# buslamp-r2.net
KiCad netlist of a schematic drawn in EAGLE
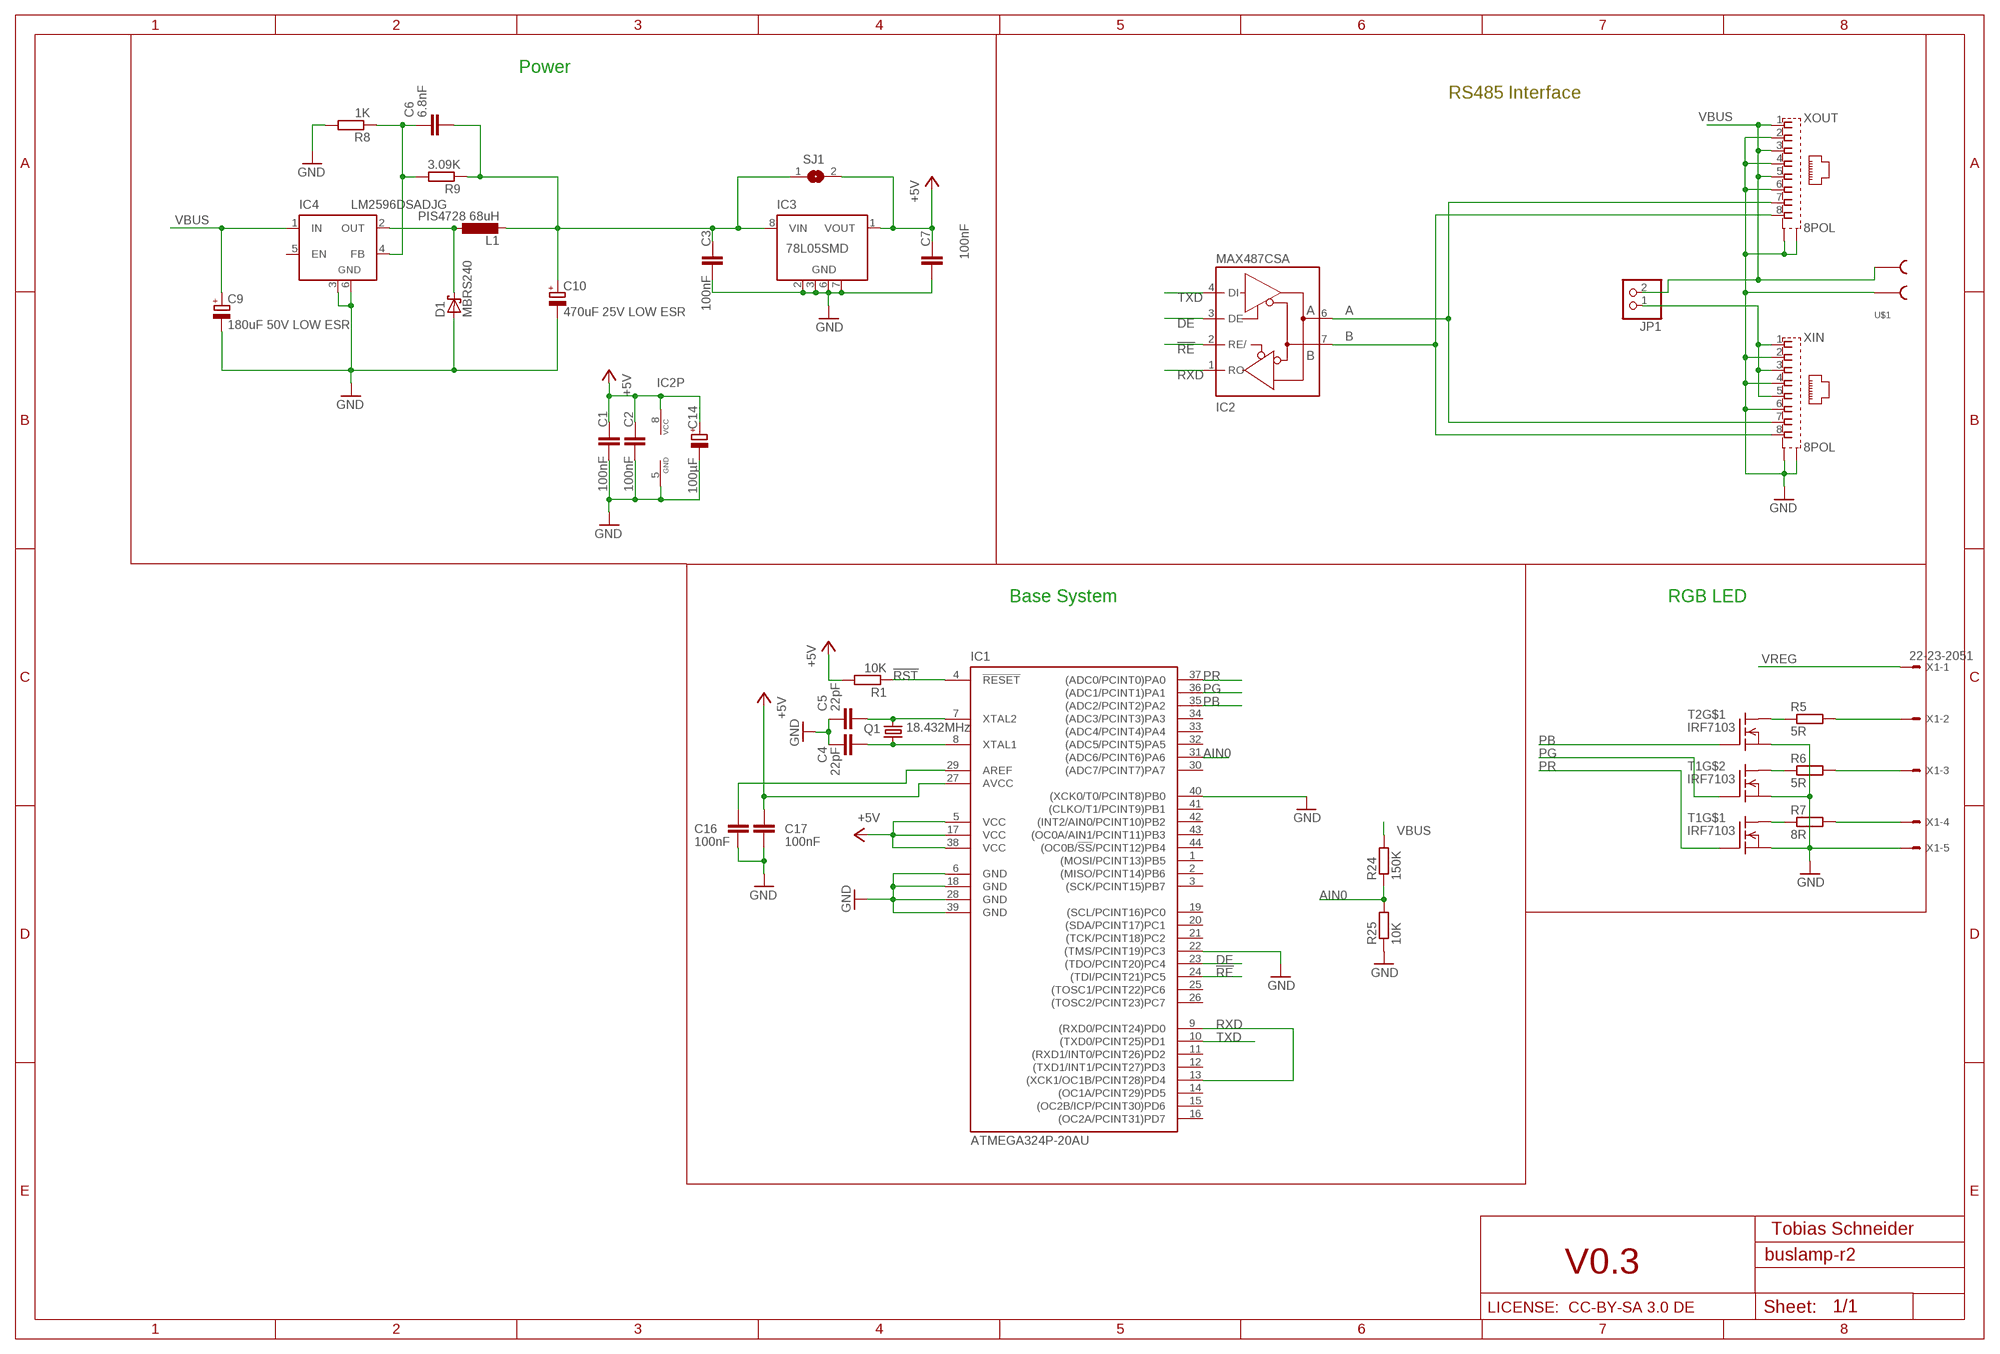
[diagram p0: schematic, sheet 1]

(export (version "E")
  (design (tool "Eeschema 10.0.6"))
  (components
    (comp (ref "C1")
      (value "100nF")
      (footprint "eagle-import:C0805K")
      (libsource (lib "eagle-import") (part "C-EUC0805K"))
    )
    (comp (ref "C2")
      (value "100nF")
      (footprint "eagle-import:C0805K")
      (libsource (lib "eagle-import") (part "C-EUC0805K"))
    )
    (comp (ref "C3")
      (value "100nF")
      (footprint "eagle-import:C0805K")
      (libsource (lib "eagle-import") (part "C-EUC0805K"))
    )
    (comp (ref "C4")
      (value "22pF")
      (footprint "eagle-import:C0805K")
      (libsource (lib "eagle-import") (part "C-EUC0805K"))
    )
    (comp (ref "C5")
      (value "22pF")
      (footprint "eagle-import:C0805K")
      (libsource (lib "eagle-import") (part "C-EUC0805K"))
    )
    (comp (ref "C6")
      (value "6.8nF")
      (footprint "eagle-import:C0805K")
      (libsource (lib "eagle-import") (part "C-EUC0805K"))
    )
    (comp (ref "C7")
      (value "100nF")
      (footprint "eagle-import:C0805K")
      (libsource (lib "eagle-import") (part "C-EUC0805K"))
    )
    (comp (ref "C9")
      (value "180uF 50V LOW ESR")
      (footprint "eagle-import:E3,5-8")
      (libsource (lib "eagle-import") (part "CPOL-EUE3.5-8"))
    )
    (comp (ref "C10")
      (value "470uF 25V LOW ESR")
      (footprint "eagle-import:E2,5-7")
      (libsource (lib "eagle-import") (part "CPOL-EUE2.5-7"))
    )
    (comp (ref "C14")
      (value "100µF")
      (footprint "eagle-import:E2,5-6")
      (libsource (lib "eagle-import") (part "CPOL-EUE2.5-6"))
    )
    (comp (ref "C16")
      (value "100nF")
      (footprint "eagle-import:C0805")
      (libsource (lib "eagle-import") (part "C-EUC0805"))
    )
    (comp (ref "C17")
      (value "100nF")
      (footprint "eagle-import:C0805")
      (libsource (lib "eagle-import") (part "C-EUC0805"))
    )
    (comp (ref "D1")
      (value "MBRS240")
      (footprint "eagle-import:SMB")
      (libsource (lib "eagle-import") (part "MBRS130LT3"))
    )
    (comp (ref "IC1")
      (value "ATMEGA324P-20AU")
      (footprint "eagle-import:TQFP44")
      (libsource (lib "eagle-import") (part "MEGA164P/324P/644P-AU"))
    )
    (comp (ref "IC2")
      (value "MAX487CSA")
      (footprint "eagle-import:SO08")
      (libsource (lib "eagle-import") (part "MAX481CSA"))
    )
    (comp (ref "IC3")
      (value "78L05SMD")
      (footprint "eagle-import:SO08")
      (libsource (lib "eagle-import") (part "78LSMD05"))
    )
    (comp (ref "IC4")
      (value "LM2596DSADJG")
      (footprint "eagle-import:TO263-5")
      (libsource (lib "eagle-import") (part "LM2596S"))
    )
    (comp (ref "JP1")
      (value "PINHD-1X2")
      (footprint "eagle-import:1X02")
      (libsource (lib "eagle-import") (part "PINHD-1X2"))
    )
    (comp (ref "L1")
      (value "PIS4728 68uH")
      (footprint "eagle-import:PIS4728")
      (libsource (lib "eagle-import") (part "PSI4728"))
    )
    (comp (ref "Q1")
      (value "18.432MHz")
      (footprint "eagle-import:HC49_S")
      (libsource (lib "eagle-import") (part "CRYTALHC49S"))
    )
    (comp (ref "R1")
      (value "10K")
      (footprint "eagle-import:M0805")
      (libsource (lib "eagle-import") (part "R-EU_M0805"))
    )
    (comp (ref "R5")
      (value "5R")
      (footprint "eagle-import:0617_17")
      (libsource (lib "eagle-import") (part "rclml_R-EU_0617/17"))
    )
    (comp (ref "R6")
      (value "5R")
      (footprint "eagle-import:0617_17")
      (libsource (lib "eagle-import") (part "rclml_R-EU_0617/17"))
    )
    (comp (ref "R7")
      (value "8R")
      (footprint "eagle-import:0617_17")
      (libsource (lib "eagle-import") (part "rclml_R-EU_0617/17"))
    )
    (comp (ref "R8")
      (value "1K")
      (footprint "eagle-import:M0805")
      (libsource (lib "eagle-import") (part "R-EU_M0805"))
    )
    (comp (ref "R9")
      (value "3.09K")
      (footprint "eagle-import:M0805")
      (libsource (lib "eagle-import") (part "R-EU_M0805"))
    )
    (comp (ref "R24")
      (value "150K")
      (footprint "eagle-import:R0805")
      (libsource (lib "eagle-import") (part "R-EU_R0805"))
    )
    (comp (ref "R25")
      (value "10K")
      (footprint "eagle-import:R0805")
      (libsource (lib "eagle-import") (part "R-EU_R0805"))
    )
    (comp (ref "SJ1") (value "SJ") (footprint "eagle-import:SJ") (libsource (lib "eagle-import") (part "SJ")))
    (comp (ref "T1")
      (value "IRF7103")
      (footprint "eagle-import:SO-8")
      (libsource (lib "eagle-import") (part "IRF7103"))
    )
    (comp (ref "T2")
      (value "IRF7103")
      (footprint "eagle-import:SO-8")
      (libsource (lib "eagle-import") (part "IRF7103"))
    )
    (comp (ref "U$1")
      (value "STL-266-2")
      (footprint "eagle-import:STL-266-2")
      (libsource (lib "eagle-import") (part "STL-266-2"))
    )
    (comp (ref "X1")
      (value "22-23-2051")
      (footprint "eagle-import:22-23-2051")
      (fields (field (name "MF") "MOLEX"))
      (libsource (lib "eagle-import") (part "22-23-2051"))
    )
    (comp (ref "XIN")
      (value "8POL")
      (footprint "eagle-import:8POL")
      (libsource (lib "eagle-import") (part "8POL"))
    )
    (comp (ref "XOUT")
      (value "8POL")
      (footprint "eagle-import:8POL")
      (libsource (lib "eagle-import") (part "8POL"))
    )
  )
  (nets
    (net (code "1") (name "+5V") (class "Default")
      (node (ref "C1") (pin "1") (pinfunction "1_1") (pintype "passive"))
      (node (ref "C14") (pin "+") (pinfunction "+_+") (pintype "passive"))
      (node (ref "C17") (pin "2") (pinfunction "2_2") (pintype "passive"))
      (node (ref "C2") (pin "1") (pinfunction "1_1") (pintype "passive"))
      (node (ref "C7") (pin "1") (pinfunction "1_1") (pintype "passive"))
      (node (ref "IC1") (pin "17") (pinfunction "VCC_17") (pintype "power_in"))
      (node (ref "IC1") (pin "27") (pinfunction "AVCC_27") (pintype "power_in"))
      (node (ref "IC1") (pin "38") (pinfunction "VCC_38") (pintype "power_in"))
      (node (ref "IC1") (pin "5") (pinfunction "VCC_5") (pintype "power_in"))
      (node (ref "IC2") (pin "8") (pinfunction "VCC_8") (pintype "power_in"))
      (node (ref "IC3") (pin "1") (pinfunction "VOUT_1") (pintype "output"))
      (node (ref "R1") (pin "2") (pinfunction "2_2") (pintype "passive"))
      (node (ref "SJ1") (pin "2") (pinfunction "2_2") (pintype "passive"))
    )
    (net (code "2") (name "/A") (class "Default")
      (node (ref "IC2") (pin "6") (pinfunction "A_6") (pintype "passive"))
      (node (ref "XIN") (pin "7") (pinfunction "7_7") (pintype "passive"))
      (node (ref "XOUT") (pin "7") (pinfunction "7_7") (pintype "passive"))
    )
    (net (code "3") (name "/AIN0") (class "Default")
      (node (ref "IC1") (pin "31") (pinfunction "(ADC6/PCINT6)PA6_31") (pintype "bidirectional"))
      (node (ref "R24") (pin "1") (pinfunction "1_1") (pintype "passive"))
      (node (ref "R25") (pin "2") (pinfunction "2_2") (pintype "passive"))
    )
    (net (code "4") (name "/B") (class "Default")
      (node (ref "IC2") (pin "7") (pinfunction "B_7") (pintype "passive"))
      (node (ref "XIN") (pin "8") (pinfunction "8_8") (pintype "passive"))
      (node (ref "XOUT") (pin "8") (pinfunction "8_8") (pintype "passive"))
    )
    (net (code "5") (name "/DE") (class "Default")
      (node (ref "IC1") (pin "23") (pinfunction "(TDO/PCINT20)PC4_23") (pintype "bidirectional"))
      (node (ref "IC2") (pin "3") (pinfunction "DE_3") (pintype "input"))
    )
    (net (code "6") (name "/PB") (class "Default")
      (node (ref "IC1") (pin "35") (pinfunction "(ADC2/PCINT2)PA2_35") (pintype "bidirectional"))
      (node (ref "T2") (pin "2") (pinfunction "G_2") (pintype "passive"))
    )
    (net (code "7") (name "/PG") (class "Default")
      (node (ref "IC1") (pin "36") (pinfunction "(ADC1/PCINT1)PA1_36") (pintype "bidirectional"))
      (node (ref "T1") (pin "4") (pinfunction "G_4") (pintype "passive"))
    )
    (net (code "8") (name "/PR") (class "Default")
      (node (ref "IC1") (pin "37") (pinfunction "(ADC0/PCINT0)PA0_37") (pintype "bidirectional"))
      (node (ref "T1") (pin "2") (pinfunction "G_2") (pintype "passive"))
    )
    (net (code "9") (name "/RXD") (class "Default")
      (node (ref "IC1") (pin "13") (pinfunction "(XCK1/OC1B/PCINT28)PD4_13") (pintype "bidirectional"))
      (node (ref "IC1") (pin "9") (pinfunction "(RXD0/PCINT24)PD0_9") (pintype "bidirectional"))
      (node (ref "IC2") (pin "1") (pinfunction "RO_1") (pintype "output"))
    )
    (net (code "10") (name "/TXD") (class "Default")
      (node (ref "IC1") (pin "10") (pinfunction "(TXD0/PCINT25)PD1_10") (pintype "bidirectional"))
      (node (ref "IC2") (pin "4") (pinfunction "DI_4") (pintype "input"))
    )
    (net (code "11") (name "/VBUS") (class "Default")
      (node (ref "C9") (pin "+") (pinfunction "+_+") (pintype "passive"))
      (node (ref "IC4") (pin "1") (pinfunction "IN_1") (pintype "input"))
      (node (ref "JP1") (pin "2") (pinfunction "2_2") (pintype "passive"))
      (node (ref "R24") (pin "2") (pinfunction "2_2") (pintype "passive"))
      (node (ref "U$1") (pin "P$4") (pinfunction "P$2_P$4") (pintype "bidirectional"))
      (node (ref "XOUT") (pin "1") (pinfunction "1_1") (pintype "passive"))
      (node (ref "XOUT") (pin "3") (pinfunction "3_3") (pintype "passive"))
      (node (ref "XOUT") (pin "5") (pinfunction "5_5") (pintype "passive"))
    )
    (net (code "12") (name "/VREG") (class "Default")
      (node (ref "C10") (pin "+") (pinfunction "+_+") (pintype "passive"))
      (node (ref "C3") (pin "1") (pinfunction "1_1") (pintype "passive"))
      (node (ref "C6") (pin "2") (pinfunction "2_2") (pintype "passive"))
      (node (ref "IC3") (pin "8") (pinfunction "VIN_8") (pintype "passive"))
      (node (ref "L1") (pin "2") (pinfunction "2_2") (pintype "passive"))
      (node (ref "R9") (pin "1") (pinfunction "1_1") (pintype "passive"))
      (node (ref "SJ1") (pin "1") (pinfunction "1_1") (pintype "passive"))
      (node (ref "X1") (pin "1") (pinfunction "S_1") (pintype "passive"))
    )
    (net (code "13") (name "/~{RE}") (class "Default")
      (node (ref "IC1") (pin "24") (pinfunction "(TDI/PCINT21)PC5_24") (pintype "bidirectional"))
      (node (ref "IC2") (pin "2") (pinfunction "RE/_2") (pintype "input"))
    )
    (net (code "14") (name "/~{RST}") (class "Default")
      (node (ref "IC1") (pin "4") (pinfunction "~{RESET}_4") (pintype "input"))
      (node (ref "R1") (pin "1") (pinfunction "1_1") (pintype "passive"))
    )
    (net (code "15") (name "GND") (class "Default")
      (node (ref "C1") (pin "2") (pinfunction "2_2") (pintype "passive"))
      (node (ref "C10") (pin "-") (pinfunction "-_-") (pintype "passive"))
      (node (ref "C14") (pin "-") (pinfunction "-_-") (pintype "passive"))
      (node (ref "C16") (pin "1") (pinfunction "1_1") (pintype "passive"))
      (node (ref "C17") (pin "1") (pinfunction "1_1") (pintype "passive"))
      (node (ref "C2") (pin "2") (pinfunction "2_2") (pintype "passive"))
      (node (ref "C3") (pin "2") (pinfunction "2_2") (pintype "passive"))
      (node (ref "C4") (pin "1") (pinfunction "1_1") (pintype "passive"))
      (node (ref "C5") (pin "1") (pinfunction "1_1") (pintype "passive"))
      (node (ref "C7") (pin "2") (pinfunction "2_2") (pintype "passive"))
      (node (ref "C9") (pin "-") (pinfunction "-_-") (pintype "passive"))
      (node (ref "D1") (pin "A") (pinfunction "A_A") (pintype "passive"))
      (node (ref "IC1") (pin "18") (pinfunction "GND_18") (pintype "power_in"))
      (node (ref "IC1") (pin "22") (pinfunction "(TMS/PCINT19)PC3_22") (pintype "bidirectional"))
      (node (ref "IC1") (pin "28") (pinfunction "GND_28") (pintype "power_in"))
      (node (ref "IC1") (pin "39") (pinfunction "GND_39") (pintype "power_in"))
      (node (ref "IC1") (pin "40") (pinfunction "(XCK0/T0/PCINT8)PB0_40") (pintype "bidirectional"))
      (node (ref "IC1") (pin "6") (pinfunction "GND_6") (pintype "power_in"))
      (node (ref "IC2") (pin "5") (pinfunction "GND_5") (pintype "power_in"))
      (node (ref "IC3") (pin "2") (pinfunction "GND_2") (pintype "power_in"))
      (node (ref "IC3") (pin "3") (pinfunction "GND_3") (pintype "power_in"))
      (node (ref "IC3") (pin "6") (pinfunction "GND_6") (pintype "power_in"))
      (node (ref "IC3") (pin "7") (pinfunction "GND_7") (pintype "power_in"))
      (node (ref "IC4") (pin "3") (pinfunction "GND_3") (pintype "power_in"))
      (node (ref "IC4") (pin "6") (pinfunction "GND_6") (pintype "power_in"))
      (node (ref "R25") (pin "1") (pinfunction "1_1") (pintype "passive"))
      (node (ref "R8") (pin "2") (pinfunction "2_2") (pintype "passive"))
      (node (ref "T1") (pin "1") (pinfunction "S_1") (pintype "passive"))
      (node (ref "T1") (pin "3") (pinfunction "S_3") (pintype "passive"))
      (node (ref "T2") (pin "1") (pinfunction "S_1") (pintype "passive"))
      (node (ref "U$1") (pin "P$3") (pinfunction "P$1_P$3") (pintype "bidirectional"))
      (node (ref "X1") (pin "5") (pinfunction "S_5") (pintype "passive"))
      (node (ref "XIN") (pin "2") (pinfunction "2_2") (pintype "passive"))
      (node (ref "XIN") (pin "4") (pinfunction "4_4") (pintype "passive"))
      (node (ref "XIN") (pin "6") (pinfunction "6_6") (pintype "passive"))
      (node (ref "XIN") (pin "S1") (pinfunction "S1_S1") (pintype "passive"))
      (node (ref "XIN") (pin "S2") (pinfunction "S2_S2") (pintype "passive"))
      (node (ref "XOUT") (pin "2") (pinfunction "2_2") (pintype "passive"))
      (node (ref "XOUT") (pin "4") (pinfunction "4_4") (pintype "passive"))
      (node (ref "XOUT") (pin "6") (pinfunction "6_6") (pintype "passive"))
      (node (ref "XOUT") (pin "S1") (pinfunction "S1_S1") (pintype "passive"))
      (node (ref "XOUT") (pin "S2") (pinfunction "S2_S2") (pintype "passive"))
    )
    (net (code "16") (name "Net-(IC1-AREF)") (class "Default")
      (node (ref "C16") (pin "2") (pinfunction "2_2") (pintype "passive"))
      (node (ref "IC1") (pin "29") (pinfunction "AREF_29") (pintype "power_in"))
    )
    (net (code "17") (name "Net-(IC1-XTAL1)") (class "Default")
      (node (ref "C4") (pin "2") (pinfunction "2_2") (pintype "passive"))
      (node (ref "IC1") (pin "8") (pinfunction "XTAL1_8") (pintype "input"))
      (node (ref "Q1") (pin "1") (pinfunction "1_1") (pintype "passive"))
    )
    (net (code "18") (name "Net-(IC1-XTAL2)") (class "Default")
      (node (ref "C5") (pin "2") (pinfunction "2_2") (pintype "passive"))
      (node (ref "IC1") (pin "7") (pinfunction "XTAL2_7") (pintype "output"))
      (node (ref "Q1") (pin "2") (pinfunction "2_2") (pintype "passive"))
    )
    (net (code "19") (name "Net-(IC4-FB)") (class "Default")
      (node (ref "C6") (pin "1") (pinfunction "1_1") (pintype "passive"))
      (node (ref "IC4") (pin "4") (pinfunction "FB_4") (pintype "input"))
      (node (ref "R8") (pin "1") (pinfunction "1_1") (pintype "passive"))
      (node (ref "R9") (pin "2") (pinfunction "2_2") (pintype "passive"))
    )
    (net (code "20") (name "Net-(IC4-OUT)") (class "Default")
      (node (ref "D1") (pin "C") (pinfunction "C_C") (pintype "passive"))
      (node (ref "IC4") (pin "2") (pinfunction "OUT_2") (pintype "output"))
      (node (ref "L1") (pin "1") (pinfunction "1_1") (pintype "passive"))
    )
    (net (code "21") (name "Net-(JP1-Pad1)") (class "Default")
      (node (ref "JP1") (pin "1") (pinfunction "1_1") (pintype "passive"))
      (node (ref "XIN") (pin "1") (pinfunction "1_1") (pintype "passive"))
      (node (ref "XIN") (pin "3") (pinfunction "3_3") (pintype "passive"))
      (node (ref "XIN") (pin "5") (pinfunction "5_5") (pintype "passive"))
    )
    (net (code "22") (name "Net-(T1A-D1)") (class "Default")
      (node (ref "R7") (pin "1") (pinfunction "1_1") (pintype "passive"))
      (node (ref "T1") (pin "8") (pinfunction "D1_8") (pintype "passive"))
    )
    (net (code "23") (name "Net-(T1B-D1)") (class "Default")
      (node (ref "R6") (pin "1") (pinfunction "1_1") (pintype "passive"))
      (node (ref "T1") (pin "5") (pinfunction "D1_5") (pintype "passive"))
    )
    (net (code "24") (name "Net-(T2A-D1)") (class "Default")
      (node (ref "R5") (pin "1") (pinfunction "1_1") (pintype "passive"))
      (node (ref "T2") (pin "8") (pinfunction "D1_8") (pintype "passive"))
    )
    (net (code "25") (name "Net-(X1B-S)") (class "Default")
      (node (ref "R5") (pin "2") (pinfunction "2_2") (pintype "passive"))
      (node (ref "X1") (pin "2") (pinfunction "S_2") (pintype "passive"))
    )
    (net (code "26") (name "Net-(X1C-S)") (class "Default")
      (node (ref "R6") (pin "2") (pinfunction "2_2") (pintype "passive"))
      (node (ref "X1") (pin "3") (pinfunction "S_3") (pintype "passive"))
    )
    (net (code "27") (name "Net-(X1D-S)") (class "Default")
      (node (ref "R7") (pin "2") (pinfunction "2_2") (pintype "passive"))
      (node (ref "X1") (pin "4") (pinfunction "S_4") (pintype "passive"))
    )
    (net (code "28") (name "unconnected-(IC1-(ADC3{slash}PCINT3)PA3-Pad34)") (class "Default")
      (node (ref "IC1") (pin "34") (pinfunction "(ADC3/PCINT3)PA3_34") (pintype "bidirectional"))
    )
    (net (code "29") (name "unconnected-(IC1-(ADC4{slash}PCINT4)PA4-Pad33)") (class "Default")
      (node (ref "IC1") (pin "33") (pinfunction "(ADC4/PCINT4)PA4_33") (pintype "bidirectional"))
    )
    (net (code "30") (name "unconnected-(IC1-(ADC5{slash}PCINT5)PA5-Pad32)") (class "Default")
      (node (ref "IC1") (pin "32") (pinfunction "(ADC5/PCINT5)PA5_32") (pintype "bidirectional"))
    )
    (net (code "31") (name "unconnected-(IC1-(ADC7{slash}PCINT7)PA7-Pad30)") (class "Default")
      (node (ref "IC1") (pin "30") (pinfunction "(ADC7/PCINT7)PA7_30") (pintype "bidirectional"))
    )
    (net (code "32") (name "unconnected-(IC1-(CLKO{slash}T1{slash}PCINT9)PB1-Pad41)") (class "Default")
      (node (ref "IC1") (pin "41") (pinfunction "(CLKO/T1/PCINT9)PB1_41") (pintype "bidirectional"))
    )
    (net (code "33") (name "unconnected-(IC1-(INT2{slash}AIN0{slash}PCINT10)PB2-Pad42)") (class "Default")
      (node (ref "IC1") (pin "42") (pinfunction "(INT2/AIN0/PCINT10)PB2_42") (pintype "bidirectional"))
    )
    (net (code "34") (name "unconnected-(IC1-(MISO{slash}PCINT14)PB6-Pad2)") (class "Default")
      (node (ref "IC1") (pin "2") (pinfunction "(MISO/PCINT14)PB6_2") (pintype "bidirectional"))
    )
    (net (code "35") (name "unconnected-(IC1-(MOSI{slash}PCINT13)PB5-Pad1)") (class "Default")
      (node (ref "IC1") (pin "1") (pinfunction "(MOSI/PCINT13)PB5_1") (pintype "bidirectional"))
    )
    (net (code "36") (name "unconnected-(IC1-(OC0A{slash}AIN1{slash}PCINT11)PB3-Pad43)") (class "Default")
      (node (ref "IC1") (pin "43") (pinfunction "(OC0A/AIN1/PCINT11)PB3_43") (pintype "bidirectional"))
    )
    (net (code "37") (name "unconnected-(IC1-(OC0B{slash}~{SS}{slash}PCINT12)PB4-Pad44)") (class "Default")
      (node (ref "IC1") (pin "44") (pinfunction "(OC0B/~{SS}/PCINT12)PB4_44") (pintype "bidirectional"))
    )
    (net (code "38") (name "unconnected-(IC1-(OC1A{slash}PCINT29)PD5-Pad14)") (class "Default")
      (node (ref "IC1") (pin "14") (pinfunction "(OC1A/PCINT29)PD5_14") (pintype "bidirectional"))
    )
    (net (code "39") (name "unconnected-(IC1-(OC2A{slash}PCINT31)PD7-Pad16)") (class "Default")
      (node (ref "IC1") (pin "16") (pinfunction "(OC2A/PCINT31)PD7_16") (pintype "bidirectional"))
    )
    (net (code "40") (name "unconnected-(IC1-(OC2B{slash}ICP{slash}PCINT30)PD6-Pad15)") (class "Default")
      (node (ref "IC1") (pin "15") (pinfunction "(OC2B/ICP/PCINT30)PD6_15") (pintype "bidirectional"))
    )
    (net (code "41") (name "unconnected-(IC1-(RXD1{slash}INT0{slash}PCINT26)PD2-Pad11)") (class "Default")
      (node (ref "IC1") (pin "11") (pinfunction "(RXD1/INT0/PCINT26)PD2_11") (pintype "bidirectional"))
    )
    (net (code "42") (name "unconnected-(IC1-(SCK{slash}PCINT15)PB7-Pad3)") (class "Default")
      (node (ref "IC1") (pin "3") (pinfunction "(SCK/PCINT15)PB7_3") (pintype "bidirectional"))
    )
    (net (code "43") (name "unconnected-(IC1-(SCL{slash}PCINT16)PC0-Pad19)") (class "Default")
      (node (ref "IC1") (pin "19") (pinfunction "(SCL/PCINT16)PC0_19") (pintype "bidirectional"))
    )
    (net (code "44") (name "unconnected-(IC1-(SDA{slash}PCINT17)PC1-Pad20)") (class "Default")
      (node (ref "IC1") (pin "20") (pinfunction "(SDA/PCINT17)PC1_20") (pintype "bidirectional"))
    )
    (net (code "45") (name "unconnected-(IC1-(TCK{slash}PCINT18)PC2-Pad21)") (class "Default")
      (node (ref "IC1") (pin "21") (pinfunction "(TCK/PCINT18)PC2_21") (pintype "bidirectional"))
    )
    (net (code "46") (name "unconnected-(IC1-(TOSC1{slash}PCINT22)PC6-Pad25)") (class "Default")
      (node (ref "IC1") (pin "25") (pinfunction "(TOSC1/PCINT22)PC6_25") (pintype "bidirectional"))
    )
    (net (code "47") (name "unconnected-(IC1-(TOSC2{slash}PCINT23)PC7-Pad26)") (class "Default")
      (node (ref "IC1") (pin "26") (pinfunction "(TOSC2/PCINT23)PC7_26") (pintype "bidirectional"))
    )
    (net (code "48") (name "unconnected-(IC1-(TXD1{slash}INT1{slash}PCINT27)PD3-Pad12)") (class "Default")
      (node (ref "IC1") (pin "12") (pinfunction "(TXD1/INT1/PCINT27)PD3_12") (pintype "bidirectional"))
    )
    (net (code "49") (name "unconnected-(IC4-EN-Pad5)") (class "Default")
      (node (ref "IC4") (pin "5") (pinfunction "EN_5") (pintype "input"))
    )
    (net (code "50") (name "unconnected-(T1A-D-Pad7)") (class "Default")
      (node (ref "T1") (pin "7") (pinfunction "D_7") (pintype "passive"))
    )
    (net (code "51") (name "unconnected-(T1B-D-Pad6)") (class "Default")
      (node (ref "T1") (pin "6") (pinfunction "D_6") (pintype "passive"))
    )
    (net (code "52") (name "unconnected-(T2A-D-Pad7)") (class "Default")
      (node (ref "T2") (pin "7") (pinfunction "D_7") (pintype "passive"))
    )
  )
)
